# Power.net
KiCad netlist of a schematic drawn in Altium Designer
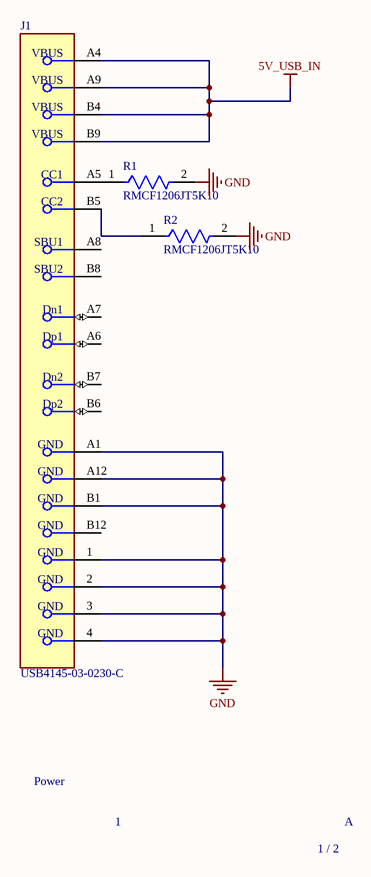
[diagram p0: Power.SchDoc]

(export (version "E")
  (design (tool "Eeschema 10.0.6"))
  (components
    (comp (ref "J1")
      (value "USB4145-03-0230-C")
      (footprint "FP-USB4145-03-0230-C-MFG")
      (description "USB4145-03-0230-C USB Connectors USB-C Rec 3u Vert 16P SMT 2.3mm TH stakes H7.46mm T+R+Cap")
      (libsource (lib "Altium Content Vault") (part "d765dcc3c904d4e46048b4fb27332a3"))
    )
    (comp (ref "R1")
      (value "RMCF1206JT5K10")
      (footprint "FP-RMCF1206-IPC_C")
      (description "5.1kΩ ±5% 0.25W 1206 Thick Film Chip Resistor AEC-Q200 compliant")
      (fields (field (name "TOLERANCE") "5%"))
      (libsource (lib "Altium Content Vault") (part "1029c3af85768c4190bb7ad29bc67b5"))
    )
    (comp (ref "R2")
      (value "RMCF1206JT5K10")
      (footprint "FP-RMCF1206-IPC_C")
      (description "5.1kΩ ±5% 0.25W 1206 Thick Film Chip Resistor AEC-Q200 compliant")
      (fields (field (name "TOLERANCE") "5%"))
      (libsource (lib "Altium Content Vault") (part "1029c3af85768c4190bb7ad29bc67b5"))
    )
  )
  (nets
    (net (code "1") (name "5V_USB_IN") (class "Default")
      (node (ref "J1") (pin "A4") (pinfunction "VBUS_A4") (pintype "power_in"))
      (node (ref "J1") (pin "A9") (pinfunction "VBUS_A9") (pintype "power_in"))
      (node (ref "J1") (pin "B4") (pinfunction "VBUS_B4") (pintype "power_in"))
      (node (ref "J1") (pin "B9") (pinfunction "VBUS_B9") (pintype "power_in"))
    )
    (net (code "2") (name "GND") (class "Default")
      (node (ref "J1") (pin "1") (pinfunction "GND_1") (pintype "power_in"))
      (node (ref "J1") (pin "2") (pinfunction "GND_2") (pintype "power_in"))
      (node (ref "J1") (pin "3") (pinfunction "GND_3") (pintype "power_in"))
      (node (ref "J1") (pin "4") (pinfunction "GND_4") (pintype "power_in"))
      (node (ref "J1") (pin "A1") (pinfunction "GND_A1") (pintype "power_in"))
      (node (ref "J1") (pin "A12") (pinfunction "GND_A12") (pintype "power_in"))
      (node (ref "J1") (pin "B1") (pinfunction "GND_B1") (pintype "power_in"))
      (node (ref "R1") (pin "2") (pinfunction "2_2") (pintype "passive"))
      (node (ref "R2") (pin "2") (pinfunction "2_2") (pintype "passive"))
    )
    (net (code "3") (name "Net-(J1-CC1)") (class "Default")
      (node (ref "J1") (pin "A5") (pinfunction "CC1_A5") (pintype "passive"))
      (node (ref "R1") (pin "1") (pinfunction "1_1") (pintype "passive"))
    )
    (net (code "4") (name "Net-(J1-CC2)") (class "Default")
      (node (ref "J1") (pin "B5") (pinfunction "CC2_B5") (pintype "passive"))
      (node (ref "R2") (pin "1") (pinfunction "1_1") (pintype "passive"))
    )
    (net (code "5") (name "unconnected-(J1-Dn1-PadA7)") (class "Default")
      (node (ref "J1") (pin "A7") (pinfunction "Dn1_A7") (pintype "bidirectional"))
    )
    (net (code "6") (name "unconnected-(J1-Dn2-PadB7)") (class "Default")
      (node (ref "J1") (pin "B7") (pinfunction "Dn2_B7") (pintype "bidirectional"))
    )
    (net (code "7") (name "unconnected-(J1-Dp1-PadA6)") (class "Default")
      (node (ref "J1") (pin "A6") (pinfunction "Dp1_A6") (pintype "bidirectional"))
    )
    (net (code "8") (name "unconnected-(J1-Dp2-PadB6)") (class "Default")
      (node (ref "J1") (pin "B6") (pinfunction "Dp2_B6") (pintype "bidirectional"))
    )
    (net (code "9") (name "unconnected-(J1-GND-PadB12)") (class "Default")
      (node (ref "J1") (pin "B12") (pinfunction "GND_B12") (pintype "power_in"))
    )
    (net (code "10") (name "unconnected-(J1-SBU1-PadA8)") (class "Default")
      (node (ref "J1") (pin "A8") (pinfunction "SBU1_A8") (pintype "passive"))
    )
    (net (code "11") (name "unconnected-(J1-SBU2-PadB8)") (class "Default")
      (node (ref "J1") (pin "B8") (pinfunction "SBU2_B8") (pintype "passive"))
    )
  )
)
